# 05_FEED.net
KiCad netlist of a schematic drawn in Altium Designer
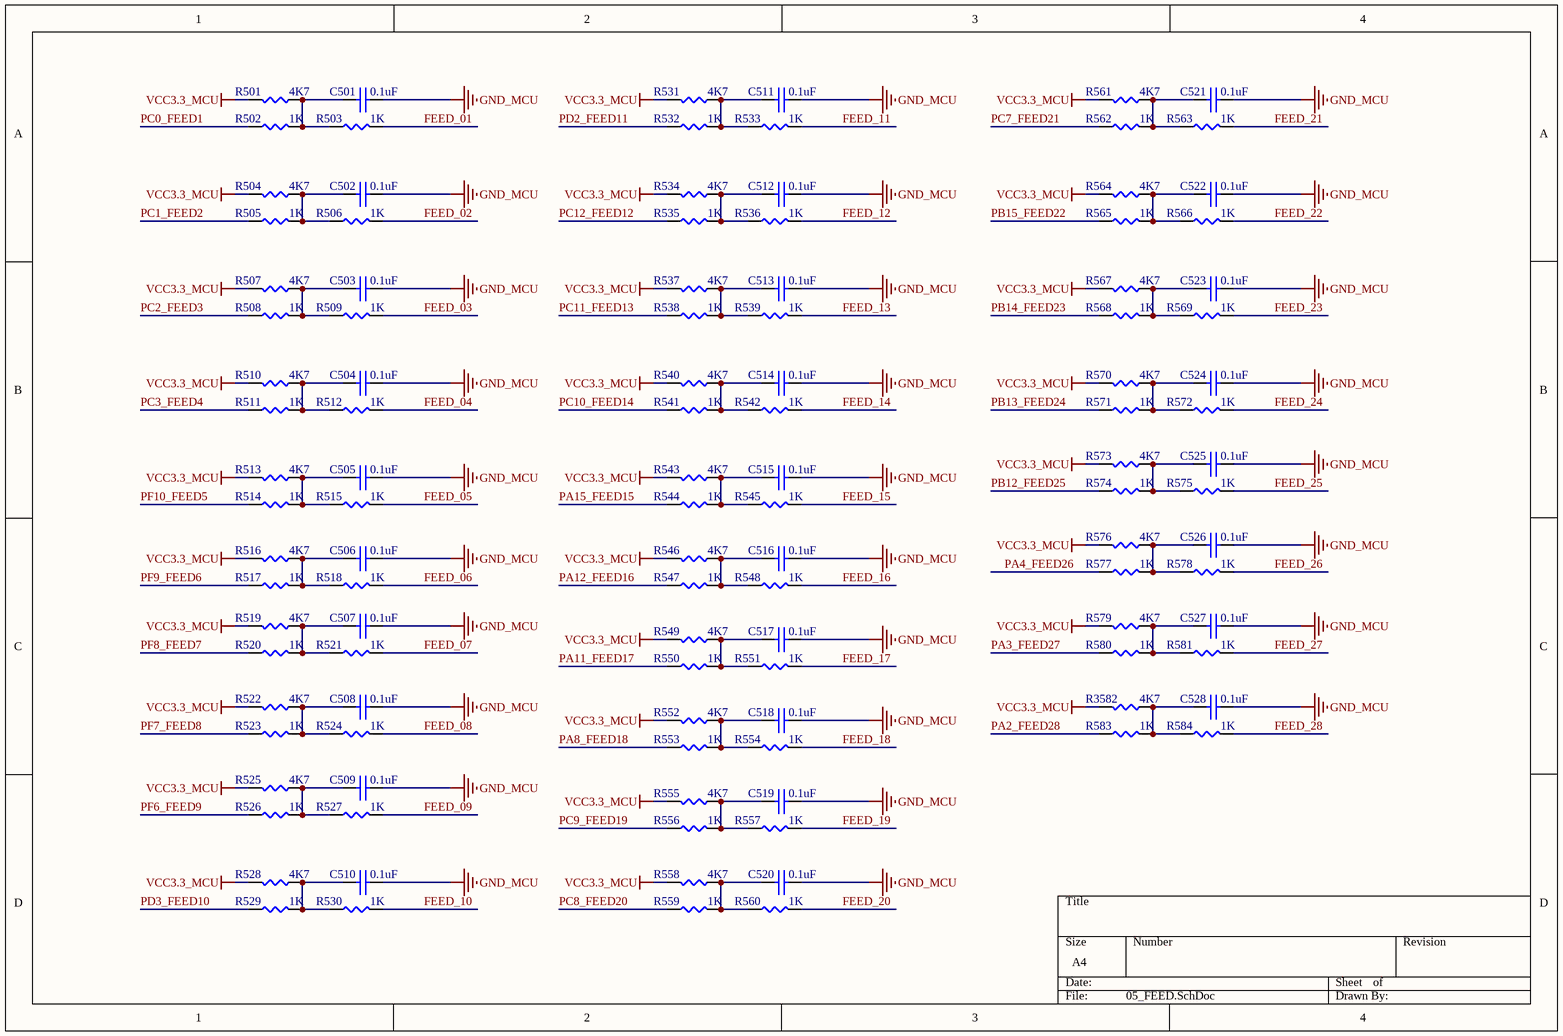
[diagram p0: 05_FEED.SchDoc]

(export (version "E")
  (design (tool "Eeschema 10.0.6"))
  (components
    (comp (ref "C501")
      (value "0.1uF")
      (footprint "CD's_LIB_2018:0603C")
      (libsource (lib "CD's_LIB_2018") (part "0603C"))
    )
    (comp (ref "C502")
      (value "0.1uF")
      (footprint "CD's_LIB_2018:0603C")
      (libsource (lib "CD's_LIB_2018") (part "0603C"))
    )
    (comp (ref "C503")
      (value "0.1uF")
      (footprint "CD's_LIB_2018:0603C")
      (libsource (lib "CD's_LIB_2018") (part "0603C"))
    )
    (comp (ref "C504")
      (value "0.1uF")
      (footprint "CD's_LIB_2018:0603C")
      (libsource (lib "CD's_LIB_2018") (part "0603C"))
    )
    (comp (ref "C505")
      (value "0.1uF")
      (footprint "CD's_LIB_2018:0603C")
      (libsource (lib "CD's_LIB_2018") (part "0603C"))
    )
    (comp (ref "C506")
      (value "0.1uF")
      (footprint "CD's_LIB_2018:0603C")
      (libsource (lib "CD's_LIB_2018") (part "0603C"))
    )
    (comp (ref "C507")
      (value "0.1uF")
      (footprint "CD's_LIB_2018:0603C")
      (libsource (lib "CD's_LIB_2018") (part "0603C"))
    )
    (comp (ref "C508")
      (value "0.1uF")
      (footprint "CD's_LIB_2018:0603C")
      (libsource (lib "CD's_LIB_2018") (part "0603C"))
    )
    (comp (ref "C509")
      (value "0.1uF")
      (footprint "CD's_LIB_2018:0603C")
      (libsource (lib "CD's_LIB_2018") (part "0603C"))
    )
    (comp (ref "C510")
      (value "0.1uF")
      (footprint "CD's_LIB_2018:0603C")
      (libsource (lib "CD's_LIB_2018") (part "0603C"))
    )
    (comp (ref "C511")
      (value "0.1uF")
      (footprint "CD's_LIB_2018:0603C")
      (libsource (lib "CD's_LIB_2018") (part "0603C"))
    )
    (comp (ref "C512")
      (value "0.1uF")
      (footprint "CD's_LIB_2018:0603C")
      (libsource (lib "CD's_LIB_2018") (part "0603C"))
    )
    (comp (ref "C513")
      (value "0.1uF")
      (footprint "CD's_LIB_2018:0603C")
      (libsource (lib "CD's_LIB_2018") (part "0603C"))
    )
    (comp (ref "C514")
      (value "0.1uF")
      (footprint "CD's_LIB_2018:0603C")
      (libsource (lib "CD's_LIB_2018") (part "0603C"))
    )
    (comp (ref "C515")
      (value "0.1uF")
      (footprint "CD's_LIB_2018:0603C")
      (libsource (lib "CD's_LIB_2018") (part "0603C"))
    )
    (comp (ref "C516")
      (value "0.1uF")
      (footprint "CD's_LIB_2018:0603C")
      (libsource (lib "CD's_LIB_2018") (part "0603C"))
    )
    (comp (ref "C517")
      (value "0.1uF")
      (footprint "CD's_LIB_2018:0603C")
      (libsource (lib "CD's_LIB_2018") (part "0603C"))
    )
    (comp (ref "C518")
      (value "0.1uF")
      (footprint "CD's_LIB_2018:0603C")
      (libsource (lib "CD's_LIB_2018") (part "0603C"))
    )
    (comp (ref "C519")
      (value "0.1uF")
      (footprint "CD's_LIB_2018:0603C")
      (libsource (lib "CD's_LIB_2018") (part "0603C"))
    )
    (comp (ref "C520")
      (value "0.1uF")
      (footprint "CD's_LIB_2018:0603C")
      (libsource (lib "CD's_LIB_2018") (part "0603C"))
    )
    (comp (ref "C521")
      (value "0.1uF")
      (footprint "CD's_LIB_2018:0603C")
      (libsource (lib "CD's_LIB_2018") (part "0603C"))
    )
    (comp (ref "C522")
      (value "0.1uF")
      (footprint "CD's_LIB_2018:0603C")
      (libsource (lib "CD's_LIB_2018") (part "0603C"))
    )
    (comp (ref "C523")
      (value "0.1uF")
      (footprint "CD's_LIB_2018:0603C")
      (libsource (lib "CD's_LIB_2018") (part "0603C"))
    )
    (comp (ref "C524")
      (value "0.1uF")
      (footprint "CD's_LIB_2018:0603C")
      (libsource (lib "CD's_LIB_2018") (part "0603C"))
    )
    (comp (ref "C525")
      (value "0.1uF")
      (footprint "CD's_LIB_2018:0603C")
      (libsource (lib "CD's_LIB_2018") (part "0603C"))
    )
    (comp (ref "C526")
      (value "0.1uF")
      (footprint "CD's_LIB_2018:0603C")
      (libsource (lib "CD's_LIB_2018") (part "0603C"))
    )
    (comp (ref "C527")
      (value "0.1uF")
      (footprint "CD's_LIB_2018:0603C")
      (libsource (lib "CD's_LIB_2018") (part "0603C"))
    )
    (comp (ref "C528")
      (value "0.1uF")
      (footprint "CD's_LIB_2018:0603C")
      (libsource (lib "CD's_LIB_2018") (part "0603C"))
    )
    (comp (ref "R501")
      (value "4K7")
      (footprint "CD's_LIB_2018:0603R")
      (libsource (lib "CD's_LIB_2018") (part "0603R"))
    )
    (comp (ref "R502")
      (value "1K")
      (footprint "CD's_LIB_2018:0603R")
      (libsource (lib "CD's_LIB_2018") (part "0603R"))
    )
    (comp (ref "R503")
      (value "1K")
      (footprint "CD's_LIB_2018:0603R")
      (libsource (lib "CD's_LIB_2018") (part "0603R"))
    )
    (comp (ref "R504")
      (value "4K7")
      (footprint "CD's_LIB_2018:0603R")
      (libsource (lib "CD's_LIB_2018") (part "0603R"))
    )
    (comp (ref "R505")
      (value "1K")
      (footprint "CD's_LIB_2018:0603R")
      (libsource (lib "CD's_LIB_2018") (part "0603R"))
    )
    (comp (ref "R506")
      (value "1K")
      (footprint "CD's_LIB_2018:0603R")
      (libsource (lib "CD's_LIB_2018") (part "0603R"))
    )
    (comp (ref "R507")
      (value "4K7")
      (footprint "CD's_LIB_2018:0603R")
      (libsource (lib "CD's_LIB_2018") (part "0603R"))
    )
    (comp (ref "R508")
      (value "1K")
      (footprint "CD's_LIB_2018:0603R")
      (libsource (lib "CD's_LIB_2018") (part "0603R"))
    )
    (comp (ref "R509")
      (value "1K")
      (footprint "CD's_LIB_2018:0603R")
      (libsource (lib "CD's_LIB_2018") (part "0603R"))
    )
    (comp (ref "R510")
      (value "4K7")
      (footprint "CD's_LIB_2018:0603R")
      (libsource (lib "CD's_LIB_2018") (part "0603R"))
    )
    (comp (ref "R511")
      (value "1K")
      (footprint "CD's_LIB_2018:0603R")
      (libsource (lib "CD's_LIB_2018") (part "0603R"))
    )
    (comp (ref "R512")
      (value "1K")
      (footprint "CD's_LIB_2018:0603R")
      (libsource (lib "CD's_LIB_2018") (part "0603R"))
    )
    (comp (ref "R513")
      (value "4K7")
      (footprint "CD's_LIB_2018:0603R")
      (libsource (lib "CD's_LIB_2018") (part "0603R"))
    )
    (comp (ref "R514")
      (value "1K")
      (footprint "CD's_LIB_2018:0603R")
      (libsource (lib "CD's_LIB_2018") (part "0603R"))
    )
    (comp (ref "R515")
      (value "1K")
      (footprint "CD's_LIB_2018:0603R")
      (libsource (lib "CD's_LIB_2018") (part "0603R"))
    )
    (comp (ref "R516")
      (value "4K7")
      (footprint "CD's_LIB_2018:0603R")
      (libsource (lib "CD's_LIB_2018") (part "0603R"))
    )
    (comp (ref "R517")
      (value "1K")
      (footprint "CD's_LIB_2018:0603R")
      (libsource (lib "CD's_LIB_2018") (part "0603R"))
    )
    (comp (ref "R518")
      (value "1K")
      (footprint "CD's_LIB_2018:0603R")
      (libsource (lib "CD's_LIB_2018") (part "0603R"))
    )
    (comp (ref "R519")
      (value "4K7")
      (footprint "CD's_LIB_2018:0603R")
      (libsource (lib "CD's_LIB_2018") (part "0603R"))
    )
    (comp (ref "R520")
      (value "1K")
      (footprint "CD's_LIB_2018:0603R")
      (libsource (lib "CD's_LIB_2018") (part "0603R"))
    )
    (comp (ref "R521")
      (value "1K")
      (footprint "CD's_LIB_2018:0603R")
      (libsource (lib "CD's_LIB_2018") (part "0603R"))
    )
    (comp (ref "R522")
      (value "4K7")
      (footprint "CD's_LIB_2018:0603R")
      (libsource (lib "CD's_LIB_2018") (part "0603R"))
    )
    (comp (ref "R523")
      (value "1K")
      (footprint "CD's_LIB_2018:0603R")
      (libsource (lib "CD's_LIB_2018") (part "0603R"))
    )
    (comp (ref "R524")
      (value "1K")
      (footprint "CD's_LIB_2018:0603R")
      (libsource (lib "CD's_LIB_2018") (part "0603R"))
    )
    (comp (ref "R525")
      (value "4K7")
      (footprint "CD's_LIB_2018:0603R")
      (libsource (lib "CD's_LIB_2018") (part "0603R"))
    )
    (comp (ref "R526")
      (value "1K")
      (footprint "CD's_LIB_2018:0603R")
      (libsource (lib "CD's_LIB_2018") (part "0603R"))
    )
    (comp (ref "R527")
      (value "1K")
      (footprint "CD's_LIB_2018:0603R")
      (libsource (lib "CD's_LIB_2018") (part "0603R"))
    )
    (comp (ref "R528")
      (value "4K7")
      (footprint "CD's_LIB_2018:0603R")
      (libsource (lib "CD's_LIB_2018") (part "0603R"))
    )
    (comp (ref "R529")
      (value "1K")
      (footprint "CD's_LIB_2018:0603R")
      (libsource (lib "CD's_LIB_2018") (part "0603R"))
    )
    (comp (ref "R530")
      (value "1K")
      (footprint "CD's_LIB_2018:0603R")
      (libsource (lib "CD's_LIB_2018") (part "0603R"))
    )
    (comp (ref "R531")
      (value "4K7")
      (footprint "CD's_LIB_2018:0603R")
      (libsource (lib "CD's_LIB_2018") (part "0603R"))
    )
    (comp (ref "R532")
      (value "1K")
      (footprint "CD's_LIB_2018:0603R")
      (libsource (lib "CD's_LIB_2018") (part "0603R"))
    )
    (comp (ref "R533")
      (value "1K")
      (footprint "CD's_LIB_2018:0603R")
      (libsource (lib "CD's_LIB_2018") (part "0603R"))
    )
    (comp (ref "R534")
      (value "4K7")
      (footprint "CD's_LIB_2018:0603R")
      (libsource (lib "CD's_LIB_2018") (part "0603R"))
    )
    (comp (ref "R535")
      (value "1K")
      (footprint "CD's_LIB_2018:0603R")
      (libsource (lib "CD's_LIB_2018") (part "0603R"))
    )
    (comp (ref "R536")
      (value "1K")
      (footprint "CD's_LIB_2018:0603R")
      (libsource (lib "CD's_LIB_2018") (part "0603R"))
    )
    (comp (ref "R537")
      (value "4K7")
      (footprint "CD's_LIB_2018:0603R")
      (libsource (lib "CD's_LIB_2018") (part "0603R"))
    )
    (comp (ref "R538")
      (value "1K")
      (footprint "CD's_LIB_2018:0603R")
      (libsource (lib "CD's_LIB_2018") (part "0603R"))
    )
    (comp (ref "R539")
      (value "1K")
      (footprint "CD's_LIB_2018:0603R")
      (libsource (lib "CD's_LIB_2018") (part "0603R"))
    )
    (comp (ref "R540")
      (value "4K7")
      (footprint "CD's_LIB_2018:0603R")
      (libsource (lib "CD's_LIB_2018") (part "0603R"))
    )
    (comp (ref "R541")
      (value "1K")
      (footprint "CD's_LIB_2018:0603R")
      (libsource (lib "CD's_LIB_2018") (part "0603R"))
    )
    (comp (ref "R542")
      (value "1K")
      (footprint "CD's_LIB_2018:0603R")
      (libsource (lib "CD's_LIB_2018") (part "0603R"))
    )
    (comp (ref "R543")
      (value "4K7")
      (footprint "CD's_LIB_2018:0603R")
      (libsource (lib "CD's_LIB_2018") (part "0603R"))
    )
    (comp (ref "R544")
      (value "1K")
      (footprint "CD's_LIB_2018:0603R")
      (libsource (lib "CD's_LIB_2018") (part "0603R"))
    )
    (comp (ref "R545")
      (value "1K")
      (footprint "CD's_LIB_2018:0603R")
      (libsource (lib "CD's_LIB_2018") (part "0603R"))
    )
    (comp (ref "R546")
      (value "4K7")
      (footprint "CD's_LIB_2018:0603R")
      (libsource (lib "CD's_LIB_2018") (part "0603R"))
    )
    (comp (ref "R547")
      (value "1K")
      (footprint "CD's_LIB_2018:0603R")
      (libsource (lib "CD's_LIB_2018") (part "0603R"))
    )
    (comp (ref "R548")
      (value "1K")
      (footprint "CD's_LIB_2018:0603R")
      (libsource (lib "CD's_LIB_2018") (part "0603R"))
    )
    (comp (ref "R549")
      (value "4K7")
      (footprint "CD's_LIB_2018:0603R")
      (libsource (lib "CD's_LIB_2018") (part "0603R"))
    )
    (comp (ref "R550")
      (value "1K")
      (footprint "CD's_LIB_2018:0603R")
      (libsource (lib "CD's_LIB_2018") (part "0603R"))
    )
    (comp (ref "R551")
      (value "1K")
      (footprint "CD's_LIB_2018:0603R")
      (libsource (lib "CD's_LIB_2018") (part "0603R"))
    )
    (comp (ref "R552")
      (value "4K7")
      (footprint "CD's_LIB_2018:0603R")
      (libsource (lib "CD's_LIB_2018") (part "0603R"))
    )
    (comp (ref "R553")
      (value "1K")
      (footprint "CD's_LIB_2018:0603R")
      (libsource (lib "CD's_LIB_2018") (part "0603R"))
    )
    (comp (ref "R554")
      (value "1K")
      (footprint "CD's_LIB_2018:0603R")
      (libsource (lib "CD's_LIB_2018") (part "0603R"))
    )
    (comp (ref "R555")
      (value "4K7")
      (footprint "CD's_LIB_2018:0603R")
      (libsource (lib "CD's_LIB_2018") (part "0603R"))
    )
    (comp (ref "R556")
      (value "1K")
      (footprint "CD's_LIB_2018:0603R")
      (libsource (lib "CD's_LIB_2018") (part "0603R"))
    )
    (comp (ref "R557")
      (value "1K")
      (footprint "CD's_LIB_2018:0603R")
      (libsource (lib "CD's_LIB_2018") (part "0603R"))
    )
    (comp (ref "R558")
      (value "4K7")
      (footprint "CD's_LIB_2018:0603R")
      (libsource (lib "CD's_LIB_2018") (part "0603R"))
    )
    (comp (ref "R559")
      (value "1K")
      (footprint "CD's_LIB_2018:0603R")
      (libsource (lib "CD's_LIB_2018") (part "0603R"))
    )
    (comp (ref "R560")
      (value "1K")
      (footprint "CD's_LIB_2018:0603R")
      (libsource (lib "CD's_LIB_2018") (part "0603R"))
    )
    (comp (ref "R561")
      (value "4K7")
      (footprint "CD's_LIB_2018:0603R")
      (libsource (lib "CD's_LIB_2018") (part "0603R"))
    )
    (comp (ref "R562")
      (value "1K")
      (footprint "CD's_LIB_2018:0603R")
      (libsource (lib "CD's_LIB_2018") (part "0603R"))
    )
    (comp (ref "R563")
      (value "1K")
      (footprint "CD's_LIB_2018:0603R")
      (libsource (lib "CD's_LIB_2018") (part "0603R"))
    )
    (comp (ref "R564")
      (value "4K7")
      (footprint "CD's_LIB_2018:0603R")
      (libsource (lib "CD's_LIB_2018") (part "0603R"))
    )
    (comp (ref "R565")
      (value "1K")
      (footprint "CD's_LIB_2018:0603R")
      (libsource (lib "CD's_LIB_2018") (part "0603R"))
    )
    (comp (ref "R566")
      (value "1K")
      (footprint "CD's_LIB_2018:0603R")
      (libsource (lib "CD's_LIB_2018") (part "0603R"))
    )
    (comp (ref "R567")
      (value "4K7")
      (footprint "CD's_LIB_2018:0603R")
      (libsource (lib "CD's_LIB_2018") (part "0603R"))
    )
    (comp (ref "R568")
      (value "1K")
      (footprint "CD's_LIB_2018:0603R")
      (libsource (lib "CD's_LIB_2018") (part "0603R"))
    )
    (comp (ref "R569")
      (value "1K")
      (footprint "CD's_LIB_2018:0603R")
      (libsource (lib "CD's_LIB_2018") (part "0603R"))
    )
    (comp (ref "R570")
      (value "4K7")
      (footprint "CD's_LIB_2018:0603R")
      (libsource (lib "CD's_LIB_2018") (part "0603R"))
    )
    (comp (ref "R571")
      (value "1K")
      (footprint "CD's_LIB_2018:0603R")
      (libsource (lib "CD's_LIB_2018") (part "0603R"))
    )
    (comp (ref "R572")
      (value "1K")
      (footprint "CD's_LIB_2018:0603R")
      (libsource (lib "CD's_LIB_2018") (part "0603R"))
    )
    (comp (ref "R573")
      (value "4K7")
      (footprint "CD's_LIB_2018:0603R")
      (libsource (lib "CD's_LIB_2018") (part "0603R"))
    )
    (comp (ref "R574")
      (value "1K")
      (footprint "CD's_LIB_2018:0603R")
      (libsource (lib "CD's_LIB_2018") (part "0603R"))
    )
    (comp (ref "R575")
      (value "1K")
      (footprint "CD's_LIB_2018:0603R")
      (libsource (lib "CD's_LIB_2018") (part "0603R"))
    )
    (comp (ref "R576")
      (value "4K7")
      (footprint "CD's_LIB_2018:0603R")
      (libsource (lib "CD's_LIB_2018") (part "0603R"))
    )
    (comp (ref "R577")
      (value "1K")
      (footprint "CD's_LIB_2018:0603R")
      (libsource (lib "CD's_LIB_2018") (part "0603R"))
    )
    (comp (ref "R578")
      (value "1K")
      (footprint "CD's_LIB_2018:0603R")
      (libsource (lib "CD's_LIB_2018") (part "0603R"))
    )
    (comp (ref "R579")
      (value "4K7")
      (footprint "CD's_LIB_2018:0603R")
      (libsource (lib "CD's_LIB_2018") (part "0603R"))
    )
    (comp (ref "R580")
      (value "1K")
      (footprint "CD's_LIB_2018:0603R")
      (libsource (lib "CD's_LIB_2018") (part "0603R"))
    )
    (comp (ref "R581")
      (value "1K")
      (footprint "CD's_LIB_2018:0603R")
      (libsource (lib "CD's_LIB_2018") (part "0603R"))
    )
    (comp (ref "R583")
      (value "1K")
      (footprint "CD's_LIB_2018:0603R")
      (libsource (lib "CD's_LIB_2018") (part "0603R"))
    )
    (comp (ref "R584")
      (value "1K")
      (footprint "CD's_LIB_2018:0603R")
      (libsource (lib "CD's_LIB_2018") (part "0603R"))
    )
    (comp (ref "R3582")
      (value "4K7")
      (footprint "CD's_LIB_2018:0603R")
      (libsource (lib "CD's_LIB_2018") (part "0603R"))
    )
  )
  (nets
    (net (code "1") (name "/FEED_01") (class "Default")
      (node (ref "R503") (pin "2") (pinfunction "2_2") (pintype "passive"))
    )
    (net (code "2") (name "/FEED_02") (class "Default")
      (node (ref "R506") (pin "2") (pinfunction "2_2") (pintype "passive"))
    )
    (net (code "3") (name "/FEED_03") (class "Default")
      (node (ref "R509") (pin "2") (pinfunction "2_2") (pintype "passive"))
    )
    (net (code "4") (name "/FEED_04") (class "Default")
      (node (ref "R512") (pin "2") (pinfunction "2_2") (pintype "passive"))
    )
    (net (code "5") (name "/FEED_05") (class "Default")
      (node (ref "R515") (pin "2") (pinfunction "2_2") (pintype "passive"))
    )
    (net (code "6") (name "/FEED_06") (class "Default")
      (node (ref "R518") (pin "2") (pinfunction "2_2") (pintype "passive"))
    )
    (net (code "7") (name "/FEED_07") (class "Default")
      (node (ref "R521") (pin "2") (pinfunction "2_2") (pintype "passive"))
    )
    (net (code "8") (name "/FEED_08") (class "Default")
      (node (ref "R524") (pin "2") (pinfunction "2_2") (pintype "passive"))
    )
    (net (code "9") (name "/FEED_09") (class "Default")
      (node (ref "R527") (pin "2") (pinfunction "2_2") (pintype "passive"))
    )
    (net (code "10") (name "/FEED_10") (class "Default")
      (node (ref "R530") (pin "2") (pinfunction "2_2") (pintype "passive"))
    )
    (net (code "11") (name "/FEED_11") (class "Default")
      (node (ref "R533") (pin "2") (pinfunction "2_2") (pintype "passive"))
    )
    (net (code "12") (name "/FEED_12") (class "Default")
      (node (ref "R536") (pin "2") (pinfunction "2_2") (pintype "passive"))
    )
    (net (code "13") (name "/FEED_13") (class "Default")
      (node (ref "R539") (pin "2") (pinfunction "2_2") (pintype "passive"))
    )
    (net (code "14") (name "/FEED_14") (class "Default")
      (node (ref "R542") (pin "2") (pinfunction "2_2") (pintype "passive"))
    )
    (net (code "15") (name "/FEED_15") (class "Default")
      (node (ref "R545") (pin "2") (pinfunction "2_2") (pintype "passive"))
    )
    (net (code "16") (name "/FEED_16") (class "Default")
      (node (ref "R548") (pin "2") (pinfunction "2_2") (pintype "passive"))
    )
    (net (code "17") (name "/FEED_17") (class "Default")
      (node (ref "R551") (pin "2") (pinfunction "2_2") (pintype "passive"))
    )
    (net (code "18") (name "/FEED_18") (class "Default")
      (node (ref "R554") (pin "2") (pinfunction "2_2") (pintype "passive"))
    )
    (net (code "19") (name "/FEED_19") (class "Default")
      (node (ref "R557") (pin "2") (pinfunction "2_2") (pintype "passive"))
    )
    (net (code "20") (name "/FEED_20") (class "Default")
      (node (ref "R560") (pin "2") (pinfunction "2_2") (pintype "passive"))
    )
    (net (code "21") (name "/FEED_21") (class "Default")
      (node (ref "R563") (pin "2") (pinfunction "2_2") (pintype "passive"))
    )
    (net (code "22") (name "/FEED_22") (class "Default")
      (node (ref "R566") (pin "2") (pinfunction "2_2") (pintype "passive"))
    )
    (net (code "23") (name "/FEED_23") (class "Default")
      (node (ref "R569") (pin "2") (pinfunction "2_2") (pintype "passive"))
    )
    (net (code "24") (name "/FEED_24") (class "Default")
      (node (ref "R572") (pin "2") (pinfunction "2_2") (pintype "passive"))
    )
    (net (code "25") (name "/FEED_25") (class "Default")
      (node (ref "R575") (pin "2") (pinfunction "2_2") (pintype "passive"))
    )
    (net (code "26") (name "/FEED_26") (class "Default")
      (node (ref "R578") (pin "2") (pinfunction "2_2") (pintype "passive"))
    )
    (net (code "27") (name "/FEED_27") (class "Default")
      (node (ref "R581") (pin "2") (pinfunction "2_2") (pintype "passive"))
    )
    (net (code "28") (name "/FEED_28") (class "Default")
      (node (ref "R584") (pin "2") (pinfunction "2_2") (pintype "passive"))
    )
    (net (code "29") (name "/PA2_FEED28") (class "Default")
      (node (ref "R583") (pin "1") (pinfunction "1_1") (pintype "passive"))
    )
    (net (code "30") (name "/PA3_FEED27") (class "Default")
      (node (ref "R580") (pin "1") (pinfunction "1_1") (pintype "passive"))
    )
    (net (code "31") (name "/PA4_FEED26") (class "Default")
      (node (ref "R577") (pin "1") (pinfunction "1_1") (pintype "passive"))
    )
    (net (code "32") (name "/PA8_FEED18") (class "Default")
      (node (ref "R553") (pin "1") (pinfunction "1_1") (pintype "passive"))
    )
    (net (code "33") (name "/PA11_FEED17") (class "Default")
      (node (ref "R550") (pin "1") (pinfunction "1_1") (pintype "passive"))
    )
    (net (code "34") (name "/PA12_FEED16") (class "Default")
      (node (ref "R547") (pin "1") (pinfunction "1_1") (pintype "passive"))
    )
    (net (code "35") (name "/PA15_FEED15") (class "Default")
      (node (ref "R544") (pin "1") (pinfunction "1_1") (pintype "passive"))
    )
    (net (code "36") (name "/PB12_FEED25") (class "Default")
      (node (ref "R574") (pin "1") (pinfunction "1_1") (pintype "passive"))
    )
    (net (code "37") (name "/PB13_FEED24") (class "Default")
      (node (ref "R571") (pin "1") (pinfunction "1_1") (pintype "passive"))
    )
    (net (code "38") (name "/PB14_FEED23") (class "Default")
      (node (ref "R568") (pin "1") (pinfunction "1_1") (pintype "passive"))
    )
    (net (code "39") (name "/PB15_FEED22") (class "Default")
      (node (ref "R565") (pin "1") (pinfunction "1_1") (pintype "passive"))
    )
    (net (code "40") (name "/PC0_FEED1") (class "Default")
      (node (ref "R502") (pin "1") (pinfunction "1_1") (pintype "passive"))
    )
    (net (code "41") (name "/PC1_FEED2") (class "Default")
      (node (ref "R505") (pin "1") (pinfunction "1_1") (pintype "passive"))
    )
    (net (code "42") (name "/PC2_FEED3") (class "Default")
      (node (ref "R508") (pin "1") (pinfunction "1_1") (pintype "passive"))
    )
    (net (code "43") (name "/PC3_FEED4") (class "Default")
      (node (ref "R511") (pin "1") (pinfunction "1_1") (pintype "passive"))
    )
    (net (code "44") (name "/PC7_FEED21") (class "Default")
      (node (ref "R562") (pin "1") (pinfunction "1_1") (pintype "passive"))
    )
    (net (code "45") (name "/PC8_FEED20") (class "Default")
      (node (ref "R559") (pin "1") (pinfunction "1_1") (pintype "passive"))
    )
    (net (code "46") (name "/PC9_FEED19") (class "Default")
      (node (ref "R556") (pin "1") (pinfunction "1_1") (pintype "passive"))
    )
    (net (code "47") (name "/PC10_FEED14") (class "Default")
      (node (ref "R541") (pin "1") (pinfunction "1_1") (pintype "passive"))
    )
    (net (code "48") (name "/PC11_FEED13") (class "Default")
      (node (ref "R538") (pin "1") (pinfunction "1_1") (pintype "passive"))
    )
    (net (code "49") (name "/PC12_FEED12") (class "Default")
      (node (ref "R535") (pin "1") (pinfunction "1_1") (pintype "passive"))
    )
    (net (code "50") (name "/PD2_FEED11") (class "Default")
      (node (ref "R532") (pin "1") (pinfunction "1_1") (pintype "passive"))
    )
    (net (code "51") (name "/PD3_FEED10") (class "Default")
      (node (ref "R529") (pin "1") (pinfunction "1_1") (pintype "passive"))
    )
    (net (code "52") (name "/PF6_FEED9") (class "Default")
      (node (ref "R526") (pin "1") (pinfunction "1_1") (pintype "passive"))
    )
    (net (code "53") (name "/PF7_FEED8") (class "Default")
      (node (ref "R523") (pin "1") (pinfunction "1_1") (pintype "passive"))
    )
    (net (code "54") (name "/PF8_FEED7") (class "Default")
      (node (ref "R520") (pin "1") (pinfunction "1_1") (pintype "passive"))
    )
    (net (code "55") (name "/PF9_FEED6") (class "Default")
      (node (ref "R517") (pin "1") (pinfunction "1_1") (pintype "passive"))
    )
    (net (code "56") (name "/PF10_FEED5") (class "Default")
      (node (ref "R514") (pin "1") (pinfunction "1_1") (pintype "passive"))
    )
    (net (code "57") (name "GND_MCU") (class "Default")
      (node (ref "C501") (pin "2") (pinfunction "2_2") (pintype "passive"))
      (node (ref "C502") (pin "2") (pinfunction "2_2") (pintype "passive"))
      (node (ref "C503") (pin "2") (pinfunction "2_2") (pintype "passive"))
      (node (ref "C504") (pin "2") (pinfunction "2_2") (pintype "passive"))
      (node (ref "C505") (pin "2") (pinfunction "2_2") (pintype "passive"))
      (node (ref "C506") (pin "2") (pinfunction "2_2") (pintype "passive"))
      (node (ref "C507") (pin "2") (pinfunction "2_2") (pintype "passive"))
      (node (ref "C508") (pin "2") (pinfunction "2_2") (pintype "passive"))
      (node (ref "C509") (pin "2") (pinfunction "2_2") (pintype "passive"))
      (node (ref "C510") (pin "2") (pinfunction "2_2") (pintype "passive"))
      (node (ref "C511") (pin "2") (pinfunction "2_2") (pintype "passive"))
      (node (ref "C512") (pin "2") (pinfunction "2_2") (pintype "passive"))
      (node (ref "C513") (pin "2") (pinfunction "2_2") (pintype "passive"))
      (node (ref "C514") (pin "2") (pinfunction "2_2") (pintype "passive"))
      (node (ref "C515") (pin "2") (pinfunction "2_2") (pintype "passive"))
      (node (ref "C516") (pin "2") (pinfunction "2_2") (pintype "passive"))
      (node (ref "C517") (pin "2") (pinfunction "2_2") (pintype "passive"))
      (node (ref "C518") (pin "2") (pinfunction "2_2") (pintype "passive"))
      (node (ref "C519") (pin "2") (pinfunction "2_2") (pintype "passive"))
      (node (ref "C520") (pin "2") (pinfunction "2_2") (pintype "passive"))
      (node (ref "C521") (pin "2") (pinfunction "2_2") (pintype "passive"))
      (node (ref "C522") (pin "2") (pinfunction "2_2") (pintype "passive"))
      (node (ref "C523") (pin "2") (pinfunction "2_2") (pintype "passive"))
      (node (ref "C524") (pin "2") (pinfunction "2_2") (pintype "passive"))
      (node (ref "C525") (pin "2") (pinfunction "2_2") (pintype "passive"))
      (node (ref "C526") (pin "2") (pinfunction "2_2") (pintype "passive"))
      (node (ref "C527") (pin "2") (pinfunction "2_2") (pintype "passive"))
      (node (ref "C528") (pin "2") (pinfunction "2_2") (pintype "passive"))
    )
    (net (code "58") (name "Net-(C501-Pad1)") (class "Default")
      (node (ref "C501") (pin "1") (pinfunction "1_1") (pintype "passive"))
      (node (ref "R501") (pin "1") (pinfunction "1_1") (pintype "passive"))
      (node (ref "R502") (pin "2") (pinfunction "2_2") (pintype "passive"))
      (node (ref "R503") (pin "1") (pinfunction "1_1") (pintype "passive"))
    )
    (net (code "59") (name "Net-(C502-Pad1)") (class "Default")
      (node (ref "C502") (pin "1") (pinfunction "1_1") (pintype "passive"))
      (node (ref "R504") (pin "1") (pinfunction "1_1") (pintype "passive"))
      (node (ref "R505") (pin "2") (pinfunction "2_2") (pintype "passive"))
      (node (ref "R506") (pin "1") (pinfunction "1_1") (pintype "passive"))
    )
    (net (code "60") (name "Net-(C503-Pad1)") (class "Default")
      (node (ref "C503") (pin "1") (pinfunction "1_1") (pintype "passive"))
      (node (ref "R507") (pin "1") (pinfunction "1_1") (pintype "passive"))
      (node (ref "R508") (pin "2") (pinfunction "2_2") (pintype "passive"))
      (node (ref "R509") (pin "1") (pinfunction "1_1") (pintype "passive"))
    )
    (net (code "61") (name "Net-(C504-Pad1)") (class "Default")
      (node (ref "C504") (pin "1") (pinfunction "1_1") (pintype "passive"))
      (node (ref "R510") (pin "1") (pinfunction "1_1") (pintype "passive"))
      (node (ref "R511") (pin "2") (pinfunction "2_2") (pintype "passive"))
      (node (ref "R512") (pin "1") (pinfunction "1_1") (pintype "passive"))
    )
    (net (code "62") (name "Net-(C505-Pad1)") (class "Default")
      (node (ref "C505") (pin "1") (pinfunction "1_1") (pintype "passive"))
      (node (ref "R513") (pin "1") (pinfunction "1_1") (pintype "passive"))
      (node (ref "R514") (pin "2") (pinfunction "2_2") (pintype "passive"))
      (node (ref "R515") (pin "1") (pinfunction "1_1") (pintype "passive"))
    )
    (net (code "63") (name "Net-(C506-Pad1)") (class "Default")
      (node (ref "C506") (pin "1") (pinfunction "1_1") (pintype "passive"))
      (node (ref "R516") (pin "1") (pinfunction "1_1") (pintype "passive"))
      (node (ref "R517") (pin "2") (pinfunction "2_2") (pintype "passive"))
      (node (ref "R518") (pin "1") (pinfunction "1_1") (pintype "passive"))
    )
    (net (code "64") (name "Net-(C507-Pad1)") (class "Default")
      (node (ref "C507") (pin "1") (pinfunction "1_1") (pintype "passive"))
      (node (ref "R519") (pin "1") (pinfunction "1_1") (pintype "passive"))
      (node (ref "R520") (pin "2") (pinfunction "2_2") (pintype "passive"))
      (node (ref "R521") (pin "1") (pinfunction "1_1") (pintype "passive"))
    )
    (net (code "65") (name "Net-(C508-Pad1)") (class "Default")
      (node (ref "C508") (pin "1") (pinfunction "1_1") (pintype "passive"))
      (node (ref "R522") (pin "1") (pinfunction "1_1") (pintype "passive"))
      (node (ref "R523") (pin "2") (pinfunction "2_2") (pintype "passive"))
      (node (ref "R524") (pin "1") (pinfunction "1_1") (pintype "passive"))
    )
    (net (code "66") (name "Net-(C509-Pad1)") (class "Default")
      (node (ref "C509") (pin "1") (pinfunction "1_1") (pintype "passive"))
      (node (ref "R525") (pin "1") (pinfunction "1_1") (pintype "passive"))
      (node (ref "R526") (pin "2") (pinfunction "2_2") (pintype "passive"))
      (node (ref "R527") (pin "1") (pinfunction "1_1") (pintype "passive"))
    )
    (net (code "67") (name "Net-(C510-Pad1)") (class "Default")
      (node (ref "C510") (pin "1") (pinfunction "1_1") (pintype "passive"))
      (node (ref "R528") (pin "1") (pinfunction "1_1") (pintype "passive"))
      (node (ref "R529") (pin "2") (pinfunction "2_2") (pintype "passive"))
      (node (ref "R530") (pin "1") (pinfunction "1_1") (pintype "passive"))
    )
    (net (code "68") (name "Net-(C511-Pad1)") (class "Default")
      (node (ref "C511") (pin "1") (pinfunction "1_1") (pintype "passive"))
      (node (ref "R531") (pin "1") (pinfunction "1_1") (pintype "passive"))
      (node (ref "R532") (pin "2") (pinfunction "2_2") (pintype "passive"))
      (node (ref "R533") (pin "1") (pinfunction "1_1") (pintype "passive"))
    )
    (net (code "69") (name "Net-(C512-Pad1)") (class "Default")
      (node (ref "C512") (pin "1") (pinfunction "1_1") (pintype "passive"))
      (node (ref "R534") (pin "1") (pinfunction "1_1") (pintype "passive"))
      (node (ref "R535") (pin "2") (pinfunction "2_2") (pintype "passive"))
      (node (ref "R536") (pin "1") (pinfunction "1_1") (pintype "passive"))
    )
    (net (code "70") (name "Net-(C513-Pad1)") (class "Default")
      (node (ref "C513") (pin "1") (pinfunction "1_1") (pintype "passive"))
      (node (ref "R537") (pin "1") (pinfunction "1_1") (pintype "passive"))
      (node (ref "R538") (pin "2") (pinfunction "2_2") (pintype "passive"))
      (node (ref "R539") (pin "1") (pinfunction "1_1") (pintype "passive"))
    )
    (net (code "71") (name "Net-(C514-Pad1)") (class "Default")
      (node (ref "C514") (pin "1") (pinfunction "1_1") (pintype "passive"))
      (node (ref "R540") (pin "1") (pinfunction "1_1") (pintype "passive"))
      (node (ref "R541") (pin "2") (pinfunction "2_2") (pintype "passive"))
      (node (ref "R542") (pin "1") (pinfunction "1_1") (pintype "passive"))
    )
    (net (code "72") (name "Net-(C515-Pad1)") (class "Default")
      (node (ref "C515") (pin "1") (pinfunction "1_1") (pintype "passive"))
      (node (ref "R543") (pin "1") (pinfunction "1_1") (pintype "passive"))
      (node (ref "R544") (pin "2") (pinfunction "2_2") (pintype "passive"))
      (node (ref "R545") (pin "1") (pinfunction "1_1") (pintype "passive"))
    )
    (net (code "73") (name "Net-(C516-Pad1)") (class "Default")
      (node (ref "C516") (pin "1") (pinfunction "1_1") (pintype "passive"))
      (node (ref "R546") (pin "1") (pinfunction "1_1") (pintype "passive"))
      (node (ref "R547") (pin "2") (pinfunction "2_2") (pintype "passive"))
      (node (ref "R548") (pin "1") (pinfunction "1_1") (pintype "passive"))
    )
    (net (code "74") (name "Net-(C517-Pad1)") (class "Default")
      (node (ref "C517") (pin "1") (pinfunction "1_1") (pintype "passive"))
      (node (ref "R549") (pin "1") (pinfunction "1_1") (pintype "passive"))
      (node (ref "R550") (pin "2") (pinfunction "2_2") (pintype "passive"))
      (node (ref "R551") (pin "1") (pinfunction "1_1") (pintype "passive"))
    )
    (net (code "75") (name "Net-(C518-Pad1)") (class "Default")
      (node (ref "C518") (pin "1") (pinfunction "1_1") (pintype "passive"))
      (node (ref "R552") (pin "1") (pinfunction "1_1") (pintype "passive"))
      (node (ref "R553") (pin "2") (pinfunction "2_2") (pintype "passive"))
      (node (ref "R554") (pin "1") (pinfunction "1_1") (pintype "passive"))
    )
    (net (code "76") (name "Net-(C519-Pad1)") (class "Default")
      (node (ref "C519") (pin "1") (pinfunction "1_1") (pintype "passive"))
      (node (ref "R555") (pin "1") (pinfunction "1_1") (pintype "passive"))
      (node (ref "R556") (pin "2") (pinfunction "2_2") (pintype "passive"))
      (node (ref "R557") (pin "1") (pinfunction "1_1") (pintype "passive"))
    )
    (net (code "77") (name "Net-(C520-Pad1)") (class "Default")
      (node (ref "C520") (pin "1") (pinfunction "1_1") (pintype "passive"))
      (node (ref "R558") (pin "1") (pinfunction "1_1") (pintype "passive"))
      (node (ref "R559") (pin "2") (pinfunction "2_2") (pintype "passive"))
      (node (ref "R560") (pin "1") (pinfunction "1_1") (pintype "passive"))
    )
    (net (code "78") (name "Net-(C521-Pad1)") (class "Default")
      (node (ref "C521") (pin "1") (pinfunction "1_1") (pintype "passive"))
      (node (ref "R561") (pin "1") (pinfunction "1_1") (pintype "passive"))
      (node (ref "R562") (pin "2") (pinfunction "2_2") (pintype "passive"))
      (node (ref "R563") (pin "1") (pinfunction "1_1") (pintype "passive"))
    )
    (net (code "79") (name "Net-(C522-Pad1)") (class "Default")
      (node (ref "C522") (pin "1") (pinfunction "1_1") (pintype "passive"))
      (node (ref "R564") (pin "1") (pinfunction "1_1") (pintype "passive"))
      (node (ref "R565") (pin "2") (pinfunction "2_2") (pintype "passive"))
      (node (ref "R566") (pin "1") (pinfunction "1_1") (pintype "passive"))
    )
    (net (code "80") (name "Net-(C523-Pad1)") (class "Default")
      (node (ref "C523") (pin "1") (pinfunction "1_1") (pintype "passive"))
      (node (ref "R567") (pin "1") (pinfunction "1_1") (pintype "passive"))
      (node (ref "R568") (pin "2") (pinfunction "2_2") (pintype "passive"))
      (node (ref "R569") (pin "1") (pinfunction "1_1") (pintype "passive"))
    )
    (net (code "81") (name "Net-(C524-Pad1)") (class "Default")
      (node (ref "C524") (pin "1") (pinfunction "1_1") (pintype "passive"))
      (node (ref "R570") (pin "1") (pinfunction "1_1") (pintype "passive"))
      (node (ref "R571") (pin "2") (pinfunction "2_2") (pintype "passive"))
      (node (ref "R572") (pin "1") (pinfunction "1_1") (pintype "passive"))
    )
    (net (code "82") (name "Net-(C525-Pad1)") (class "Default")
      (node (ref "C525") (pin "1") (pinfunction "1_1") (pintype "passive"))
      (node (ref "R573") (pin "1") (pinfunction "1_1") (pintype "passive"))
      (node (ref "R574") (pin "2") (pinfunction "2_2") (pintype "passive"))
      (node (ref "R575") (pin "1") (pinfunction "1_1") (pintype "passive"))
    )
    (net (code "83") (name "Net-(C526-Pad1)") (class "Default")
      (node (ref "C526") (pin "1") (pinfunction "1_1") (pintype "passive"))
      (node (ref "R576") (pin "1") (pinfunction "1_1") (pintype "passive"))
      (node (ref "R577") (pin "2") (pinfunction "2_2") (pintype "passive"))
      (node (ref "R578") (pin "1") (pinfunction "1_1") (pintype "passive"))
    )
    (net (code "84") (name "Net-(C527-Pad1)") (class "Default")
      (node (ref "C527") (pin "1") (pinfunction "1_1") (pintype "passive"))
      (node (ref "R579") (pin "1") (pinfunction "1_1") (pintype "passive"))
      (node (ref "R580") (pin "2") (pinfunction "2_2") (pintype "passive"))
      (node (ref "R581") (pin "1") (pinfunction "1_1") (pintype "passive"))
    )
    (net (code "85") (name "Net-(C528-Pad1)") (class "Default")
      (node (ref "C528") (pin "1") (pinfunction "1_1") (pintype "passive"))
      (node (ref "R3582") (pin "1") (pinfunction "1_1") (pintype "passive"))
      (node (ref "R583") (pin "2") (pinfunction "2_2") (pintype "passive"))
      (node (ref "R584") (pin "1") (pinfunction "1_1") (pintype "passive"))
    )
    (net (code "86") (name "VCC3.3_MCU") (class "Default")
      (node (ref "R3582") (pin "2") (pinfunction "2_2") (pintype "passive"))
      (node (ref "R501") (pin "2") (pinfunction "2_2") (pintype "passive"))
      (node (ref "R504") (pin "2") (pinfunction "2_2") (pintype "passive"))
      (node (ref "R507") (pin "2") (pinfunction "2_2") (pintype "passive"))
      (node (ref "R510") (pin "2") (pinfunction "2_2") (pintype "passive"))
      (node (ref "R513") (pin "2") (pinfunction "2_2") (pintype "passive"))
      (node (ref "R516") (pin "2") (pinfunction "2_2") (pintype "passive"))
      (node (ref "R519") (pin "2") (pinfunction "2_2") (pintype "passive"))
      (node (ref "R522") (pin "2") (pinfunction "2_2") (pintype "passive"))
      (node (ref "R525") (pin "2") (pinfunction "2_2") (pintype "passive"))
      (node (ref "R528") (pin "2") (pinfunction "2_2") (pintype "passive"))
      (node (ref "R531") (pin "2") (pinfunction "2_2") (pintype "passive"))
      (node (ref "R534") (pin "2") (pinfunction "2_2") (pintype "passive"))
      (node (ref "R537") (pin "2") (pinfunction "2_2") (pintype "passive"))
      (node (ref "R540") (pin "2") (pinfunction "2_2") (pintype "passive"))
      (node (ref "R543") (pin "2") (pinfunction "2_2") (pintype "passive"))
      (node (ref "R546") (pin "2") (pinfunction "2_2") (pintype "passive"))
      (node (ref "R549") (pin "2") (pinfunction "2_2") (pintype "passive"))
      (node (ref "R552") (pin "2") (pinfunction "2_2") (pintype "passive"))
      (node (ref "R555") (pin "2") (pinfunction "2_2") (pintype "passive"))
      (node (ref "R558") (pin "2") (pinfunction "2_2") (pintype "passive"))
      (node (ref "R561") (pin "2") (pinfunction "2_2") (pintype "passive"))
      (node (ref "R564") (pin "2") (pinfunction "2_2") (pintype "passive"))
      (node (ref "R567") (pin "2") (pinfunction "2_2") (pintype "passive"))
      (node (ref "R570") (pin "2") (pinfunction "2_2") (pintype "passive"))
      (node (ref "R573") (pin "2") (pinfunction "2_2") (pintype "passive"))
      (node (ref "R576") (pin "2") (pinfunction "2_2") (pintype "passive"))
      (node (ref "R579") (pin "2") (pinfunction "2_2") (pintype "passive"))
    )
  )
)
